# MainBoard_MCU_Power.net
KiCad netlist of a schematic drawn in Altium Designer
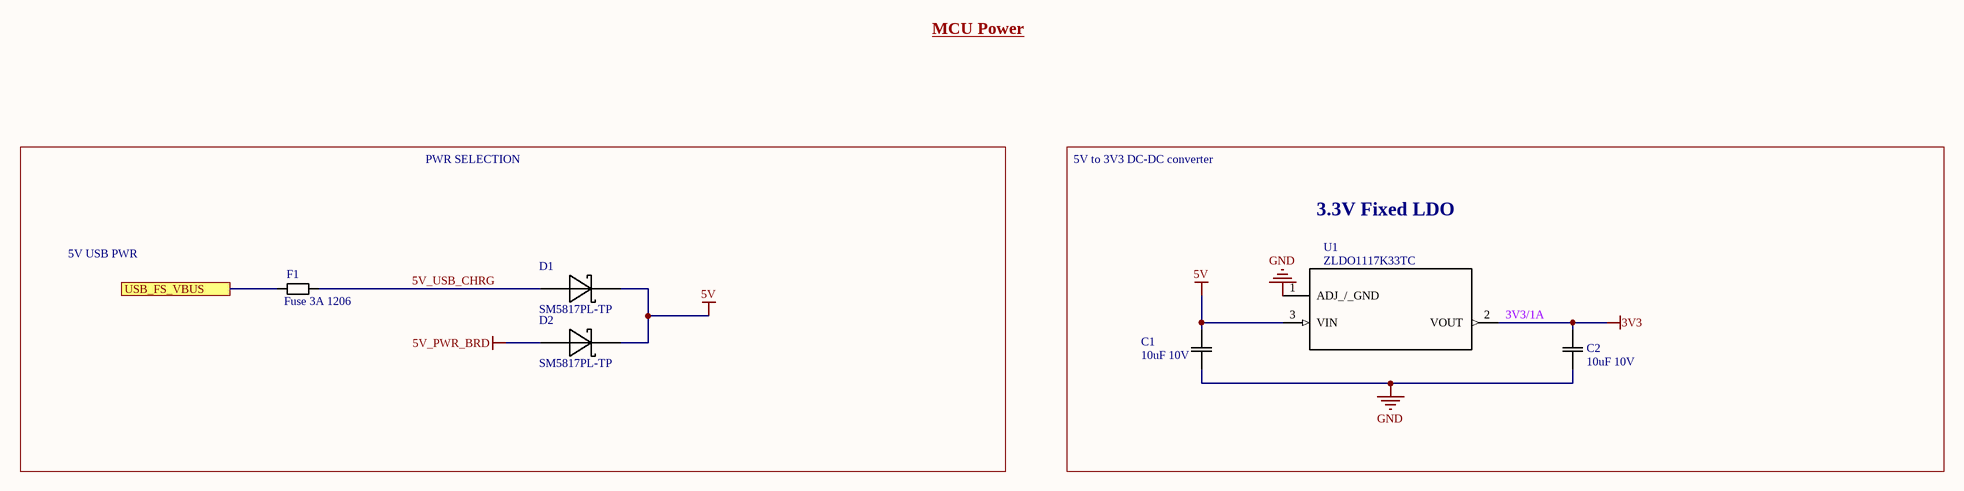
[diagram p0: MainBoard_MCU_Power.SchDoc]

(export (version "E")
  (design (tool "Eeschema 10.0.6"))
  (components
    (comp (ref "C1")
      (value "10uF 10V")
      (footprint "0603")
      (description "CAP CER 10UF 10V X5R 0805")
      (fields (field (name "TOLERANCE") "10%"))
      (libsource (lib "AltiumLibraries") (part "CAP 10uF 10V"))
    )
    (comp (ref "C2")
      (value "10uF 10V")
      (footprint "0603")
      (description "CAP CER 10UF 10V X5R 0805")
      (fields (field (name "TOLERANCE") "10%"))
      (libsource (lib "AltiumLibraries") (part "CAP 10uF 10V"))
    )
    (comp (ref "D1")
      (value "SM5817PL-TP")
      (footprint "SOD-123")
      (description "Diode Schottky 20V 1A Surface Mount SOD-123FL")
      (fields (field (name "MF") "Micro Commercial Co"))
      (libsource (lib "AltiumLibraries") (part "DIODE SCHOTTKY 20V 1A"))
    )
    (comp (ref "D2")
      (value "SM5817PL-TP")
      (footprint "SOD-123")
      (description "Diode Schottky 20V 1A Surface Mount SOD-123FL")
      (fields (field (name "MF") "Micro Commercial Co"))
      (libsource (lib "AltiumLibraries") (part "DIODE SCHOTTKY 20V 1A"))
    )
    (comp (ref "F1")
      (value "Fuse 3A 1206")
      (footprint "1206")
      (description "FUSE 3A 63V AC/DC SLOW 1206")
      (libsource (lib "AltiumLibraries") (part "FUSE 3A 63V SLOW"))
    )
    (comp (ref "U1")
      (value "ZLDO1117K33TC")
      (footprint "DPAK (TO-252)")
      (description "Linear Voltage Regulator IC Positive Fixed 1 Output  1A TO-252-3")
      (fields (field (name "MF") "Diodes Incorporated"))
      (libsource (lib "AltiumLibraries") (part "ZLDO1117K33TC"))
    )
  )
  (nets
    (net (code "1") (name "/5V_USB_CHRG") (class "Default")
      (node (ref "D1") (pin "A") (pinfunction "A_A") (pintype "passive"))
      (node (ref "F1") (pin "2") (pinfunction "2_2") (pintype "passive"))
    )
    (net (code "2") (name "/USB_FS_VBUS") (class "Default")
      (node (ref "F1") (pin "1") (pinfunction "1_1") (pintype "passive"))
    )
    (net (code "3") (name "3V3") (class "Default")
      (node (ref "C2") (pin "1") (pinfunction "C1_1") (pintype "passive"))
      (node (ref "U1") (pin "2") (pinfunction "VOUT_2") (pintype "output"))
    )
    (net (code "4") (name "5V") (class "Default")
      (node (ref "C1") (pin "1") (pinfunction "C1_1") (pintype "passive"))
      (node (ref "D1") (pin "C") (pinfunction "K_C") (pintype "passive"))
      (node (ref "D2") (pin "C") (pinfunction "K_C") (pintype "passive"))
      (node (ref "U1") (pin "3") (pinfunction "VIN_3") (pintype "input"))
    )
    (net (code "5") (name "5V_PWR_BRD") (class "Default")
      (node (ref "D2") (pin "A") (pinfunction "A_A") (pintype "passive"))
    )
    (net (code "6") (name "GND") (class "Default")
      (node (ref "C1") (pin "2") (pinfunction "C2_2") (pintype "passive"))
      (node (ref "C2") (pin "2") (pinfunction "C2_2") (pintype "passive"))
      (node (ref "U1") (pin "1") (pinfunction "ADJ_/_GND_1") (pintype "power_in"))
    )
  )
)
